# ServoShield.net
KiCad netlist of a schematic drawn in EAGLE
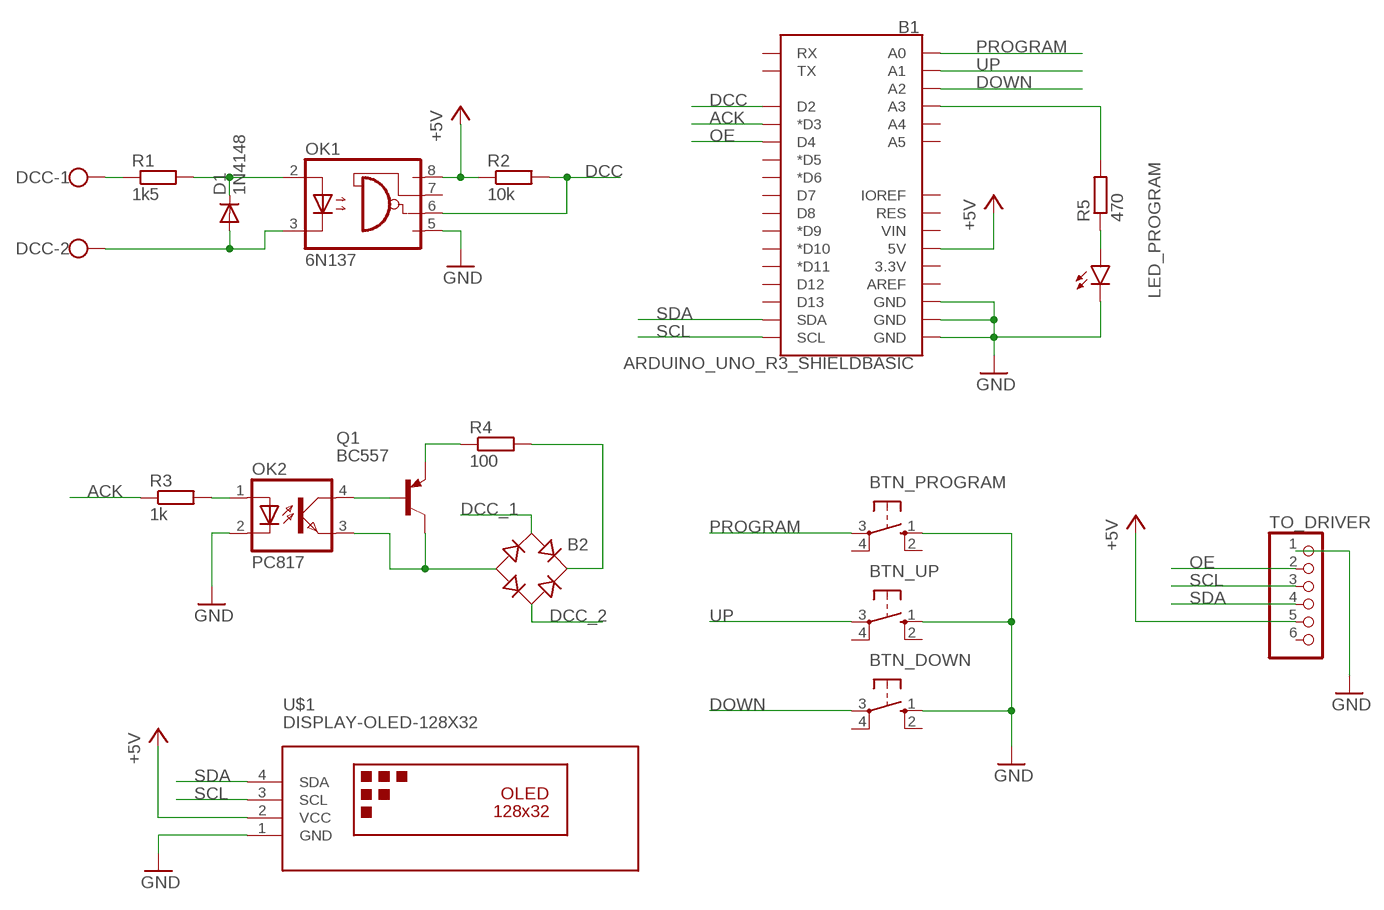
[diagram p0: schematic, sheet 1]

(export (version "E")
  (design (tool "Eeschema 10.0.6"))
  (components
    (comp (ref "B1")
      (value "ARDUINO_UNO_R3_SHIELDBASIC")
      (footprint "eagle-import:UNO_R3_SHIELD")
      (libsource (lib "eagle-import") (part "ARDUINO_UNO_R3_SHIELDBASIC"))
    )
    (comp (ref "B2")
      (value "RB1A")
      (footprint "eagle-import:RB1A")
      (libsource (lib "eagle-import") (part "RB1A"))
    )
    (comp (ref "BTN_DOWN")
      (value "10-XX")
      (footprint "eagle-import:B3F-10XX")
      (fields (field (name "MPN") "B3F-1000"))
      (libsource (lib "eagle-import") (part "10-XX"))
    )
    (comp (ref "BTN_PROGRAM")
      (value "10-XX")
      (footprint "eagle-import:B3F-10XX")
      (fields (field (name "MPN") "B3F-1000"))
      (libsource (lib "eagle-import") (part "10-XX"))
    )
    (comp (ref "BTN_UP")
      (value "10-XX")
      (footprint "eagle-import:B3F-10XX")
      (fields (field (name "MPN") "B3F-1000"))
      (libsource (lib "eagle-import") (part "10-XX"))
    )
    (comp (ref "D1")
      (value "1N4148")
      (footprint "eagle-import:DO35-7")
      (libsource (lib "eagle-import") (part "1N4148DO35-7"))
    )
    (comp (ref "DCC")
      (value "W237-102")
      (footprint "eagle-import:W237-102")
      (fields (field (name "MPN") "237-102"))
      (libsource (lib "eagle-import") (part "W237-102"))
    )
    (comp (ref "LED_PROGRAM")
      (value "LED3MM")
      (footprint "eagle-import:LED3MM")
      (libsource (lib "eagle-import") (part "LED3MM"))
    )
    (comp (ref "OK1")
      (value "6N137")
      (footprint "eagle-import:DIL08")
      (libsource (lib "eagle-import") (part "6N137"))
    )
    (comp (ref "OK2")
      (value "PC817")
      (footprint "eagle-import:DIL04")
      (fields (field (name "MPN") "PC817X4J000F"))
      (libsource (lib "eagle-import") (part "PC817"))
    )
    (comp (ref "Q1")
      (value "BC557")
      (footprint "eagle-import:TO92")
      (libsource (lib "eagle-import") (part "BC557"))
    )
    (comp (ref "R1")
      (value "1k5")
      (footprint "eagle-import:0207_2V")
      (libsource (lib "eagle-import") (part "R-EU_0207/2V"))
    )
    (comp (ref "R2")
      (value "10k")
      (footprint "eagle-import:0207_2V")
      (libsource (lib "eagle-import") (part "R-EU_0207/2V"))
    )
    (comp (ref "R3")
      (value "1k")
      (footprint "eagle-import:0207_2V")
      (libsource (lib "eagle-import") (part "R-EU_0207/2V"))
    )
    (comp (ref "R4")
      (value "100")
      (footprint "eagle-import:0207_2V")
      (libsource (lib "eagle-import") (part "R-EU_0207/2V"))
    )
    (comp (ref "R5")
      (value "470")
      (footprint "eagle-import:0207_2V")
      (libsource (lib "eagle-import") (part "R-EU_0207/2V"))
    )
    (comp (ref "TO_DRIVER")
      (value "PINHD-1X6")
      (footprint "eagle-import:1X06")
      (libsource (lib "eagle-import") (part "PINHD-1X6"))
    )
    (comp (ref "U$1")
      (value "DISPLAY-OLED-128X32")
      (footprint "eagle-import:DISPLAY-OLED-128X32")
      (libsource (lib "eagle-import") (part "DISPLAY-OLED-128X32"))
    )
  )
  (nets
    (net (code "1") (name "+5V") (class "Default")
      (node (ref "B1") (pin "5V") (pinfunction "5V_5V") (pintype "bidirectional"))
      (node (ref "OK1") (pin "8") (pinfunction "VCC_8") (pintype "passive"))
      (node (ref "R2") (pin "1") (pinfunction "1_1") (pintype "passive"))
      (node (ref "TO_DRIVER") (pin "5") (pinfunction "5_5") (pintype "passive"))
      (node (ref "U$1") (pin "2") (pinfunction "VCC_2") (pintype "power_in"))
    )
    (net (code "2") (name "/ACK") (class "Default")
      (node (ref "B1") (pin "D3") (pinfunction "*D3_D3") (pintype "bidirectional"))
      (node (ref "R3") (pin "1") (pinfunction "1_1") (pintype "passive"))
    )
    (net (code "3") (name "/DCC") (class "Default")
      (node (ref "B1") (pin "D2") (pinfunction "D2_D2") (pintype "bidirectional"))
      (node (ref "OK1") (pin "6") (pinfunction "VO_6") (pintype "passive"))
      (node (ref "R2") (pin "2") (pinfunction "2_2") (pintype "passive"))
    )
    (net (code "4") (name "/DCC_1") (class "Default")
      (node (ref "B2") (pin "AC1") (pinfunction "AC1_AC1") (pintype "passive"))
      (node (ref "DCC") (pin "1") (pinfunction "KL_1") (pintype "passive"))
      (node (ref "R1") (pin "1") (pinfunction "1_1") (pintype "passive"))
    )
    (net (code "5") (name "/DCC_2") (class "Default")
      (node (ref "B2") (pin "AC2") (pinfunction "AC2_AC2") (pintype "passive"))
      (node (ref "D1") (pin "A") (pinfunction "A_A") (pintype "passive"))
      (node (ref "DCC") (pin "2") (pinfunction "KL_2") (pintype "passive"))
      (node (ref "OK1") (pin "3") (pinfunction "C_3") (pintype "passive"))
    )
    (net (code "6") (name "/DOWN") (class "Default")
      (node (ref "B1") (pin "A2") (pinfunction "A2_A2") (pintype "bidirectional"))
      (node (ref "BTN_DOWN") (pin "3") (pinfunction "P_3") (pintype "passive"))
    )
    (net (code "7") (name "/OE") (class "Default")
      (node (ref "B1") (pin "D4") (pinfunction "D4_D4") (pintype "bidirectional"))
      (node (ref "TO_DRIVER") (pin "2") (pinfunction "2_2") (pintype "passive"))
    )
    (net (code "8") (name "/PROGRAM") (class "Default")
      (node (ref "B1") (pin "A0") (pinfunction "A0_A0") (pintype "bidirectional"))
      (node (ref "BTN_PROGRAM") (pin "3") (pinfunction "P_3") (pintype "passive"))
    )
    (net (code "9") (name "/SCL") (class "Default")
      (node (ref "B1") (pin "SCL") (pinfunction "SCL_SCL") (pintype "bidirectional"))
      (node (ref "TO_DRIVER") (pin "3") (pinfunction "3_3") (pintype "passive"))
      (node (ref "U$1") (pin "3") (pinfunction "SCL_3") (pintype "bidirectional"))
    )
    (net (code "10") (name "/SDA") (class "Default")
      (node (ref "B1") (pin "SDA") (pinfunction "SDA_SDA") (pintype "bidirectional"))
      (node (ref "TO_DRIVER") (pin "4") (pinfunction "4_4") (pintype "passive"))
      (node (ref "U$1") (pin "4") (pinfunction "SDA_4") (pintype "bidirectional"))
    )
    (net (code "11") (name "/UP") (class "Default")
      (node (ref "B1") (pin "A1") (pinfunction "A1_A1") (pintype "bidirectional"))
      (node (ref "BTN_UP") (pin "3") (pinfunction "P_3") (pintype "passive"))
    )
    (net (code "12") (name "GND") (class "Default")
      (node (ref "B1") (pin "GND@0") (pinfunction "GND_GND@0") (pintype "bidirectional"))
      (node (ref "B1") (pin "GND@1") (pinfunction "GND_GND@1") (pintype "bidirectional"))
      (node (ref "B1") (pin "GND@2") (pinfunction "GND_GND@2") (pintype "bidirectional"))
      (node (ref "BTN_DOWN") (pin "1") (pinfunction "S_1") (pintype "passive"))
      (node (ref "BTN_PROGRAM") (pin "1") (pinfunction "S_1") (pintype "passive"))
      (node (ref "BTN_UP") (pin "1") (pinfunction "S_1") (pintype "passive"))
      (node (ref "LED_PROGRAM") (pin "K") (pinfunction "C_K") (pintype "passive"))
      (node (ref "OK1") (pin "5") (pinfunction "GND_5") (pintype "passive"))
      (node (ref "OK2") (pin "2") (pinfunction "C_2") (pintype "passive"))
      (node (ref "TO_DRIVER") (pin "1") (pinfunction "1_1") (pintype "passive"))
      (node (ref "U$1") (pin "1") (pinfunction "GND_1") (pintype "power_in"))
    )
    (net (code "13") (name "Net-(B1-PadA3)") (class "Default")
      (node (ref "B1") (pin "A3") (pinfunction "A3_A3") (pintype "bidirectional"))
      (node (ref "R5") (pin "2") (pinfunction "2_2") (pintype "passive"))
    )
    (net (code "14") (name "Net-(B2-Pad+)") (class "Default")
      (node (ref "B2") (pin "+") (pinfunction "+_+") (pintype "passive"))
      (node (ref "R4") (pin "2") (pinfunction "2_2") (pintype "passive"))
    )
    (net (code "15") (name "Net-(LED_PROGRAM-PadA)") (class "Default")
      (node (ref "LED_PROGRAM") (pin "A") (pinfunction "A_A") (pintype "passive"))
      (node (ref "R5") (pin "1") (pinfunction "1_1") (pintype "passive"))
    )
    (net (code "16") (name "Net-(OK1-A)") (class "Default")
      (node (ref "D1") (pin "C") (pinfunction "C_C") (pintype "passive"))
      (node (ref "OK1") (pin "2") (pinfunction "A_2") (pintype "passive"))
      (node (ref "R1") (pin "2") (pinfunction "2_2") (pintype "passive"))
    )
    (net (code "17") (name "Net-(OK2-A)") (class "Default")
      (node (ref "OK2") (pin "1") (pinfunction "A_1") (pintype "passive"))
      (node (ref "R3") (pin "2") (pinfunction "2_2") (pintype "passive"))
    )
    (net (code "18") (name "Net-(OK2-COL)") (class "Default")
      (node (ref "OK2") (pin "4") (pinfunction "COL_4") (pintype "passive"))
      (node (ref "Q1") (pin "2") (pinfunction "B_2") (pintype "passive"))
    )
    (net (code "19") (name "Net-(OK2-EMIT)") (class "Default")
      (node (ref "B2") (pin "-") (pinfunction "-_-") (pintype "passive"))
      (node (ref "OK2") (pin "3") (pinfunction "EMIT_3") (pintype "passive"))
      (node (ref "Q1") (pin "3") (pinfunction "C_3") (pintype "passive"))
    )
    (net (code "20") (name "Net-(Q1-E)") (class "Default")
      (node (ref "Q1") (pin "1") (pinfunction "E_1") (pintype "passive"))
      (node (ref "R4") (pin "1") (pinfunction "1_1") (pintype "passive"))
    )
    (net (code "21") (name "unconnected-(B1-*D5-PadD5)") (class "Default")
      (node (ref "B1") (pin "D5") (pinfunction "*D5_D5") (pintype "bidirectional"))
    )
    (net (code "22") (name "unconnected-(B1-*D6-PadD6)") (class "Default")
      (node (ref "B1") (pin "D6") (pinfunction "*D6_D6") (pintype "bidirectional"))
    )
    (net (code "23") (name "unconnected-(B1-*D9-PadD9)") (class "Default")
      (node (ref "B1") (pin "D9") (pinfunction "*D9_D9") (pintype "bidirectional"))
    )
    (net (code "24") (name "unconnected-(B1-*D10-PadD10)") (class "Default")
      (node (ref "B1") (pin "D10") (pinfunction "*D10_D10") (pintype "bidirectional"))
    )
    (net (code "25") (name "unconnected-(B1-*D11-PadD11)") (class "Default")
      (node (ref "B1") (pin "D11") (pinfunction "*D11_D11") (pintype "bidirectional"))
    )
    (net (code "26") (name "unconnected-(B1-Pad3.3V)") (class "Default")
      (node (ref "B1") (pin "3.3V") (pinfunction "3.3V_3.3V") (pintype "bidirectional"))
    )
    (net (code "27") (name "unconnected-(B1-PadA4)") (class "Default")
      (node (ref "B1") (pin "A4") (pinfunction "A4_A4") (pintype "bidirectional"))
    )
    (net (code "28") (name "unconnected-(B1-PadA5)") (class "Default")
      (node (ref "B1") (pin "A5") (pinfunction "A5_A5") (pintype "bidirectional"))
    )
    (net (code "29") (name "unconnected-(B1-PadAREF)") (class "Default")
      (node (ref "B1") (pin "AREF") (pinfunction "AREF_AREF") (pintype "bidirectional"))
    )
    (net (code "30") (name "unconnected-(B1-PadD7)") (class "Default")
      (node (ref "B1") (pin "D7") (pinfunction "D7_D7") (pintype "bidirectional"))
    )
    (net (code "31") (name "unconnected-(B1-PadD8)") (class "Default")
      (node (ref "B1") (pin "D8") (pinfunction "D8_D8") (pintype "bidirectional"))
    )
    (net (code "32") (name "unconnected-(B1-PadD12)") (class "Default")
      (node (ref "B1") (pin "D12") (pinfunction "D12_D12") (pintype "bidirectional"))
    )
    (net (code "33") (name "unconnected-(B1-PadD13)") (class "Default")
      (node (ref "B1") (pin "D13") (pinfunction "D13_D13") (pintype "bidirectional"))
    )
    (net (code "34") (name "unconnected-(B1-PadIOREF)") (class "Default")
      (node (ref "B1") (pin "IOREF") (pinfunction "IOREF_IOREF") (pintype "bidirectional"))
    )
    (net (code "35") (name "unconnected-(B1-PadRES)") (class "Default")
      (node (ref "B1") (pin "RES") (pinfunction "RES_RES") (pintype "bidirectional"))
    )
    (net (code "36") (name "unconnected-(B1-PadRX)") (class "Default")
      (node (ref "B1") (pin "RX") (pinfunction "RX_RX") (pintype "bidirectional"))
    )
    (net (code "37") (name "unconnected-(B1-PadTX)") (class "Default")
      (node (ref "B1") (pin "TX") (pinfunction "TX_TX") (pintype "bidirectional"))
    )
    (net (code "38") (name "unconnected-(B1-PadVIN)") (class "Default")
      (node (ref "B1") (pin "VIN") (pinfunction "VIN_VIN") (pintype "bidirectional"))
    )
    (net (code "39") (name "unconnected-(BTN_DOWN-P1-Pad4)") (class "Default")
      (node (ref "BTN_DOWN") (pin "4") (pinfunction "P1_4") (pintype "passive"))
    )
    (net (code "40") (name "unconnected-(BTN_DOWN-S1-Pad2)") (class "Default")
      (node (ref "BTN_DOWN") (pin "2") (pinfunction "S1_2") (pintype "passive"))
    )
    (net (code "41") (name "unconnected-(BTN_PROGRAM-P1-Pad4)") (class "Default")
      (node (ref "BTN_PROGRAM") (pin "4") (pinfunction "P1_4") (pintype "passive"))
    )
    (net (code "42") (name "unconnected-(BTN_PROGRAM-S1-Pad2)") (class "Default")
      (node (ref "BTN_PROGRAM") (pin "2") (pinfunction "S1_2") (pintype "passive"))
    )
    (net (code "43") (name "unconnected-(BTN_UP-P1-Pad4)") (class "Default")
      (node (ref "BTN_UP") (pin "4") (pinfunction "P1_4") (pintype "passive"))
    )
    (net (code "44") (name "unconnected-(BTN_UP-S1-Pad2)") (class "Default")
      (node (ref "BTN_UP") (pin "2") (pinfunction "S1_2") (pintype "passive"))
    )
    (net (code "45") (name "unconnected-(OK1-VE-Pad7)") (class "Default")
      (node (ref "OK1") (pin "7") (pinfunction "VE_7") (pintype "passive"))
    )
    (net (code "46") (name "unconnected-(TO_DRIVER-Pad6)") (class "Default")
      (node (ref "TO_DRIVER") (pin "6") (pinfunction "6_6") (pintype "passive"))
    )
  )
)
